# Driver.net
KiCad netlist of a schematic drawn in Altium Designer
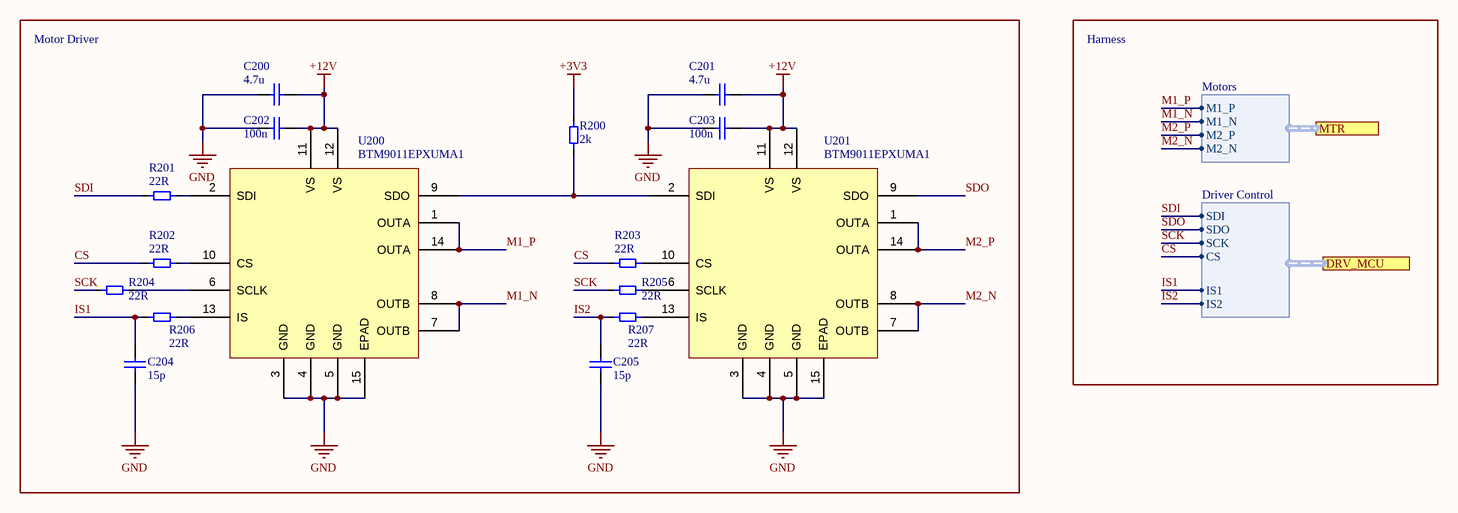
[diagram p0: Driver.SchDoc]

(export (version "E")
  (design (tool "Eeschema 10.0.6"))
  (components
    (comp (ref "C200")
      (value "4.7u")
      (footprint "MLCC_0603_M")
      (description "MLCC, 0603, 4.7u, 10%, 35V, X5R")
      (fields (field (name "TOLERANCE") "10%") (field (name "VOLTAGE") "35V"))
      (libsource (lib "Krakul Vault") (part "CAPACITOR_NONPOL_IEC"))
    )
    (comp (ref "C201")
      (value "4.7u")
      (footprint "MLCC_0603_M")
      (description "MLCC, 0603, 4.7u, 10%, 35V, X5R")
      (fields (field (name "TOLERANCE") "10%") (field (name "VOLTAGE") "35V"))
      (libsource (lib "Krakul Vault") (part "CAPACITOR_NONPOL_IEC"))
    )
    (comp (ref "C202")
      (value "100n")
      (footprint "MLCC_0603_M")
      (description "MLCC, 0603, 100n, 10%, 35V, X7R")
      (fields (field (name "MANUFACTURER") "Any") (field (name "VOLTAGE") "35V"))
      (libsource (lib "Krakul Vault") (part "CAPACITOR_NONPOL_IEC"))
    )
    (comp (ref "C203")
      (value "100n")
      (footprint "MLCC_0603_M")
      (description "MLCC, 0603, 100n, 10%, 35V, X7R")
      (fields (field (name "MANUFACTURER") "Any") (field (name "VOLTAGE") "35V"))
      (libsource (lib "Krakul Vault") (part "CAPACITOR_NONPOL_IEC"))
    )
    (comp (ref "C204")
      (value "15p")
      (footprint "MLCC_0603_M")
      (description "MLCC, 0603, 15p, 5%, 50V, C0G/NP0")
      (fields (field (name "MANUFACTURER") "Any") (field (name "VOLTAGE") "50V"))
      (libsource (lib "Krakul Vault") (part "CAPACITOR_NONPOL_IEC"))
    )
    (comp (ref "C205")
      (value "15p")
      (footprint "MLCC_0603_M")
      (description "MLCC, 0603, 15p, 5%, 50V, C0G/NP0")
      (fields (field (name "MANUFACTURER") "Any") (field (name "VOLTAGE") "50V"))
      (libsource (lib "Krakul Vault") (part "CAPACITOR_NONPOL_IEC"))
    )
    (comp (ref "R200")
      (value "2k")
      (footprint "Resistor_0603_M")
      (description "Resistor, 0603, 2k, 1%, 1/10W")
      (fields (field (name "MANUFACTURER") "Any") (field (name "POWER") "100mW"))
      (libsource (lib "Krakul Vault") (part "RESISTOR_GENERIC_IEC"))
    )
    (comp (ref "R201")
      (value "22R")
      (footprint "Resistor_0603_M")
      (description "Resistor, 0603, 22R, 1%, 1/10W")
      (fields (field (name "TOLERANCE") "1%") (field (name "MANUFACTURER") "Any"))
      (libsource (lib "Krakul Vault") (part "RESISTOR_GENERIC_IEC"))
    )
    (comp (ref "R202")
      (value "22R")
      (footprint "Resistor_0603_M")
      (description "Resistor, 0603, 22R, 1%, 1/10W")
      (fields (field (name "TOLERANCE") "1%") (field (name "MANUFACTURER") "Any"))
      (libsource (lib "Krakul Vault") (part "RESISTOR_GENERIC_IEC"))
    )
    (comp (ref "R203")
      (value "22R")
      (footprint "Resistor_0603_M")
      (description "Resistor, 0603, 22R, 1%, 1/10W")
      (fields (field (name "TOLERANCE") "1%") (field (name "MANUFACTURER") "Any"))
      (libsource (lib "Krakul Vault") (part "RESISTOR_GENERIC_IEC"))
    )
    (comp (ref "R204")
      (value "22R")
      (footprint "Resistor_0603_M")
      (description "Resistor, 0603, 22R, 1%, 1/10W")
      (fields (field (name "TOLERANCE") "1%") (field (name "MANUFACTURER") "Any"))
      (libsource (lib "Krakul Vault") (part "RESISTOR_GENERIC_IEC"))
    )
    (comp (ref "R205")
      (value "22R")
      (footprint "Resistor_0603_M")
      (description "Resistor, 0603, 22R, 1%, 1/10W")
      (fields (field (name "TOLERANCE") "1%") (field (name "MANUFACTURER") "Any"))
      (libsource (lib "Krakul Vault") (part "RESISTOR_GENERIC_IEC"))
    )
    (comp (ref "R206")
      (value "22R")
      (footprint "Resistor_0603_M")
      (description "Resistor, 0603, 22R, 1%, 1/10W")
      (fields (field (name "TOLERANCE") "1%") (field (name "MANUFACTURER") "Any"))
      (libsource (lib "Krakul Vault") (part "RESISTOR_GENERIC_IEC"))
    )
    (comp (ref "R207")
      (value "22R")
      (footprint "Resistor_0603_M")
      (description "Resistor, 0603, 22R, 1%, 1/10W")
      (fields (field (name "TOLERANCE") "1%") (field (name "MANUFACTURER") "Any"))
      (libsource (lib "Krakul Vault") (part "RESISTOR_GENERIC_IEC"))
    )
    (comp (ref "U200")
      (value "BTM9011EPXUMA1")
      (footprint "BTM9011EPXUMA1")
      (description "DC Mtr Drive, Brush, 150DEGC, TSSOPEP-14 Rohs Compliant: Yes")
      (fields (field (name "MANUFACTURER") "Infineon Technologies"))
      (libsource (lib "Krakul Vault") (part "BTM9011EPXUMA1"))
    )
    (comp (ref "U201")
      (value "BTM9011EPXUMA1")
      (footprint "BTM9011EPXUMA1")
      (description "DC Mtr Drive, Brush, 150DEGC, TSSOPEP-14 Rohs Compliant: Yes")
      (fields (field (name "MANUFACTURER") "Infineon Technologies"))
      (libsource (lib "Krakul Vault") (part "BTM9011EPXUMA1"))
    )
  )
  (nets
    (net (code "4") (name "+3V3") (class "Default")
      (node (ref "R200") (pin "2") (pinfunction "2_2") (pintype "passive"))
    )
    (net (code "5") (name "+12V") (class "Default")
      (node (ref "C200") (pin "2") (pinfunction "2_2") (pintype "passive"))
      (node (ref "C201") (pin "2") (pinfunction "2_2") (pintype "passive"))
      (node (ref "C202") (pin "2") (pinfunction "2_2") (pintype "passive"))
      (node (ref "C203") (pin "2") (pinfunction "2_2") (pintype "passive"))
      (node (ref "U200") (pin "11") (pinfunction "VS_11") (pintype "passive"))
      (node (ref "U200") (pin "12") (pinfunction "VS_12") (pintype "passive"))
      (node (ref "U201") (pin "11") (pinfunction "VS_11") (pintype "passive"))
      (node (ref "U201") (pin "12") (pinfunction "VS_12") (pintype "passive"))
    )
    (net (code "6") (name "/CS") (class "Default")
      (node (ref "R202") (pin "1") (pinfunction "1_1") (pintype "passive"))
      (node (ref "R203") (pin "1") (pinfunction "1_1") (pintype "passive"))
    )
    (net (code "7") (name "/IS1") (class "Default")
      (node (ref "C204") (pin "1") (pinfunction "1_1") (pintype "passive"))
      (node (ref "R206") (pin "1") (pinfunction "1_1") (pintype "passive"))
    )
    (net (code "8") (name "/IS2") (class "Default")
      (node (ref "C205") (pin "1") (pinfunction "1_1") (pintype "passive"))
      (node (ref "R207") (pin "1") (pinfunction "1_1") (pintype "passive"))
    )
    (net (code "9") (name "/M1_N") (class "Default")
      (node (ref "U200") (pin "7") (pinfunction "OUTB_7") (pintype "passive"))
      (node (ref "U200") (pin "8") (pinfunction "OUTB_8") (pintype "passive"))
    )
    (net (code "10") (name "/M1_P") (class "Default")
      (node (ref "U200") (pin "1") (pinfunction "OUTA_1") (pintype "passive"))
      (node (ref "U200") (pin "14") (pinfunction "OUTA_14") (pintype "passive"))
    )
    (net (code "11") (name "/M2_N") (class "Default")
      (node (ref "U201") (pin "7") (pinfunction "OUTB_7") (pintype "passive"))
      (node (ref "U201") (pin "8") (pinfunction "OUTB_8") (pintype "passive"))
    )
    (net (code "12") (name "/M2_P") (class "Default")
      (node (ref "U201") (pin "1") (pinfunction "OUTA_1") (pintype "passive"))
      (node (ref "U201") (pin "14") (pinfunction "OUTA_14") (pintype "passive"))
    )
    (net (code "13") (name "/SCK") (class "Default")
      (node (ref "R204") (pin "1") (pinfunction "1_1") (pintype "passive"))
      (node (ref "R205") (pin "1") (pinfunction "1_1") (pintype "passive"))
    )
    (net (code "14") (name "/SDI") (class "Default")
      (node (ref "R201") (pin "1") (pinfunction "1_1") (pintype "passive"))
    )
    (net (code "15") (name "/SDO") (class "Default")
      (node (ref "U201") (pin "9") (pinfunction "SDO_9") (pintype "passive"))
    )
    (net (code "18") (name "GND") (class "Default")
      (node (ref "C200") (pin "1") (pinfunction "1_1") (pintype "passive"))
      (node (ref "C201") (pin "1") (pinfunction "1_1") (pintype "passive"))
      (node (ref "C202") (pin "1") (pinfunction "1_1") (pintype "passive"))
      (node (ref "C203") (pin "1") (pinfunction "1_1") (pintype "passive"))
      (node (ref "C204") (pin "2") (pinfunction "2_2") (pintype "passive"))
      (node (ref "C205") (pin "2") (pinfunction "2_2") (pintype "passive"))
      (node (ref "U200") (pin "15") (pinfunction "EPAD_15") (pintype "passive"))
      (node (ref "U200") (pin "3") (pinfunction "GND_3") (pintype "passive"))
      (node (ref "U200") (pin "4") (pinfunction "GND_4") (pintype "passive"))
      (node (ref "U200") (pin "5") (pinfunction "GND_5") (pintype "passive"))
      (node (ref "U201") (pin "15") (pinfunction "EPAD_15") (pintype "passive"))
      (node (ref "U201") (pin "3") (pinfunction "GND_3") (pintype "passive"))
      (node (ref "U201") (pin "4") (pinfunction "GND_4") (pintype "passive"))
      (node (ref "U201") (pin "5") (pinfunction "GND_5") (pintype "passive"))
    )
    (net (code "19") (name "Net-(U200-CS)") (class "Default")
      (node (ref "R202") (pin "2") (pinfunction "2_2") (pintype "passive"))
      (node (ref "U200") (pin "10") (pinfunction "CS_10") (pintype "passive"))
    )
    (net (code "20") (name "Net-(U200-IS)") (class "Default")
      (node (ref "R206") (pin "2") (pinfunction "2_2") (pintype "passive"))
      (node (ref "U200") (pin "13") (pinfunction "IS_13") (pintype "passive"))
    )
    (net (code "21") (name "Net-(U200-SCLK)") (class "Default")
      (node (ref "R204") (pin "2") (pinfunction "2_2") (pintype "passive"))
      (node (ref "U200") (pin "6") (pinfunction "SCLK_6") (pintype "passive"))
    )
    (net (code "22") (name "Net-(U200-SDI)") (class "Default")
      (node (ref "R201") (pin "2") (pinfunction "2_2") (pintype "passive"))
      (node (ref "U200") (pin "2") (pinfunction "SDI_2") (pintype "passive"))
    )
    (net (code "23") (name "Net-(U200-SDO)") (class "Default")
      (node (ref "R200") (pin "1") (pinfunction "1_1") (pintype "passive"))
      (node (ref "U200") (pin "9") (pinfunction "SDO_9") (pintype "passive"))
      (node (ref "U201") (pin "2") (pinfunction "SDI_2") (pintype "passive"))
    )
    (net (code "24") (name "Net-(U201-CS)") (class "Default")
      (node (ref "R203") (pin "2") (pinfunction "2_2") (pintype "passive"))
      (node (ref "U201") (pin "10") (pinfunction "CS_10") (pintype "passive"))
    )
    (net (code "25") (name "Net-(U201-IS)") (class "Default")
      (node (ref "R207") (pin "2") (pinfunction "2_2") (pintype "passive"))
      (node (ref "U201") (pin "13") (pinfunction "IS_13") (pintype "passive"))
    )
    (net (code "26") (name "Net-(U201-SCLK)") (class "Default")
      (node (ref "R205") (pin "2") (pinfunction "2_2") (pintype "passive"))
      (node (ref "U201") (pin "6") (pinfunction "SCLK_6") (pintype "passive"))
    )
  )
)
